# fonteV2.net
KiCad netlist of a schematic drawn in EAGLE
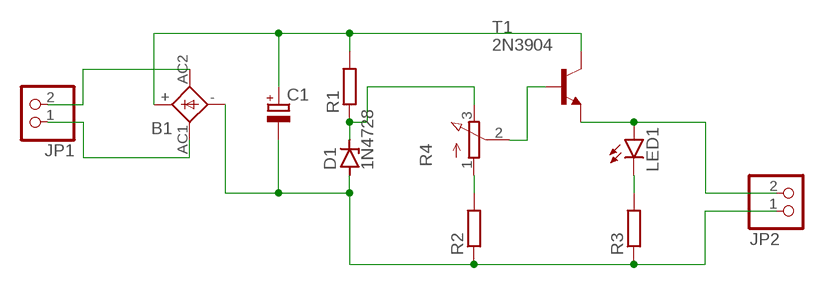
[diagram p0: schematic, sheet 1]

(export (version "E")
  (design (tool "Eeschema 10.0.6"))
  (components
    (comp (ref "B1")
      (value "1KAB")
      (footprint "eagle-import:1KAB")
      (libsource (lib "eagle-import") (part "1KAB"))
    )
    (comp (ref "C1")
      (value "CPOL-EUE3.5-10")
      (footprint "eagle-import:E3,5-10")
      (libsource (lib "eagle-import") (part "CPOL-EUE3.5-10"))
    )
    (comp (ref "D1")
      (value "1N4728")
      (footprint "eagle-import:DO41Z10")
      (libsource (lib "eagle-import") (part "1N4728"))
    )
    (comp (ref "JP1")
      (value "PINHD-1X2")
      (footprint "eagle-import:1X02")
      (libsource (lib "eagle-import") (part "PINHD-1X2"))
    )
    (comp (ref "JP2")
      (value "PINHD-1X2")
      (footprint "eagle-import:1X02")
      (libsource (lib "eagle-import") (part "PINHD-1X2"))
    )
    (comp (ref "LED1")
      (value "LED5MM")
      (footprint "eagle-import:LED5MM")
      (libsource (lib "eagle-import") (part "LED5MM"))
    )
    (comp (ref "R1")
      (value "R-EU_0207/10")
      (footprint "eagle-import:0207_10")
      (libsource (lib "eagle-import") (part "R-EU_0207/10"))
    )
    (comp (ref "R2")
      (value "R-EU_0207/10")
      (footprint "eagle-import:0207_10")
      (libsource (lib "eagle-import") (part "R-EU_0207/10"))
    )
    (comp (ref "R3")
      (value "R-EU_0207/10")
      (footprint "eagle-import:0207_10")
      (libsource (lib "eagle-import") (part "R-EU_0207/10"))
    )
    (comp (ref "R4")
      (value "3RP/1610N")
      (footprint "eagle-import:3RP_1610N")
      (libsource (lib "eagle-import") (part "3RP/1610N"))
    )
    (comp (ref "T1")
      (value "2N3904")
      (footprint "eagle-import:TO92")
      (libsource (lib "eagle-import") (part "2N3904"))
    )
  )
  (nets
    (net (code "1") (name "Net-(B1-Pad-)") (class "Default")
      (node (ref "B1") (pin "-") (pinfunction "-_-") (pintype "passive"))
      (node (ref "C1") (pin "-") (pinfunction "-_-") (pintype "passive"))
      (node (ref "D1") (pin "A") (pinfunction "A_A") (pintype "passive"))
      (node (ref "JP2") (pin "1") (pinfunction "1_1") (pintype "passive"))
      (node (ref "R2") (pin "1") (pinfunction "1_1") (pintype "passive"))
      (node (ref "R3") (pin "1") (pinfunction "1_1") (pintype "passive"))
    )
    (net (code "2") (name "Net-(B1-PadAC1)") (class "Default")
      (node (ref "B1") (pin "AC1") (pinfunction "AC1_AC1") (pintype "passive"))
      (node (ref "JP1") (pin "1") (pinfunction "1_1") (pintype "passive"))
    )
    (net (code "3") (name "Net-(B1-PadAC2)") (class "Default")
      (node (ref "B1") (pin "AC2") (pinfunction "AC2_AC2") (pintype "passive"))
      (node (ref "JP1") (pin "2") (pinfunction "2_2") (pintype "passive"))
    )
    (net (code "4") (name "Net-(LED1-C)") (class "Default")
      (node (ref "LED1") (pin "K") (pinfunction "C_K") (pintype "passive"))
      (node (ref "R3") (pin "2") (pinfunction "2_2") (pintype "passive"))
    )
    (net (code "5") (name "Net-(R4-A)") (class "Default")
      (node (ref "R2") (pin "2") (pinfunction "2_2") (pintype "passive"))
      (node (ref "R4") (pin "1") (pinfunction "A_1") (pintype "passive"))
    )
    (net (code "6") (name "Net-(R4-E)") (class "Default")
      (node (ref "D1") (pin "C") (pinfunction "C_C") (pintype "passive"))
      (node (ref "R1") (pin "1") (pinfunction "1_1") (pintype "passive"))
      (node (ref "R4") (pin "3") (pinfunction "E_3") (pintype "passive"))
    )
    (net (code "7") (name "Net-(R4-S)") (class "Default")
      (node (ref "R4") (pin "2") (pinfunction "S_2") (pintype "passive"))
      (node (ref "T1") (pin "2") (pinfunction "B_2") (pintype "passive"))
    )
    (net (code "8") (name "Net-(T1-C)") (class "Default")
      (node (ref "B1") (pin "+") (pinfunction "+_+") (pintype "passive"))
      (node (ref "C1") (pin "+") (pinfunction "+_+") (pintype "passive"))
      (node (ref "R1") (pin "2") (pinfunction "2_2") (pintype "passive"))
      (node (ref "T1") (pin "1") (pinfunction "C_1") (pintype "passive"))
    )
    (net (code "9") (name "Net-(T1-E)") (class "Default")
      (node (ref "JP2") (pin "2") (pinfunction "2_2") (pintype "passive"))
      (node (ref "LED1") (pin "A") (pinfunction "A_A") (pintype "passive"))
      (node (ref "T1") (pin "3") (pinfunction "E_3") (pintype "passive"))
    )
  )
)
